# Reguladores.net
KiCad netlist of a schematic drawn in Altium Designer
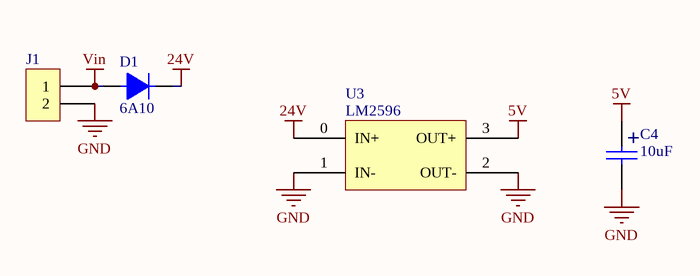
[diagram p0: Reguladores.SchDoc]

(export (version "E")
  (design (tool "Eeschema 10.0.6"))
  (components
    (comp (ref "C4") (value "10uF") (footprint "CAP.ELEC") (libsource (lib "LIBPIOIX") (part "CAPPOL")))
    (comp (ref "D1") (value "6A10") (footprint "DO214AC") (libsource (lib "LIBPIOIX") (part "DIODO")))
    (comp (ref "J1")
      (value "BORNERA 2")
      (footprint "BORNERA2")
      (libsource (lib "LIBPIOIX") (part "BORNERA 2"))
    )
    (comp (ref "U3")
      (value "LM2596")
      (footprint "LM2596 DC TO DC CONVERTER MODULE")
      (libsource (lib "Esquematicos") (part "LM2596"))
    )
  )
  (nets
    (net (code "1") (name "5V") (class "Default")
      (node (ref "C4") (pin "1") (pinfunction "1_1") (pintype "passive"))
      (node (ref "U3") (pin "3") (pinfunction "OUT+_3") (pintype "passive"))
    )
    (net (code "2") (name "24V") (class "Default")
      (node (ref "D1") (pin "2") (pinfunction "2_2") (pintype "passive"))
      (node (ref "U3") (pin "0") (pinfunction "IN+_0") (pintype "passive"))
    )
    (net (code "3") (name "GND") (class "Default")
      (node (ref "C4") (pin "2") (pinfunction "2_2") (pintype "passive"))
      (node (ref "J1") (pin "2") (pinfunction "2_2") (pintype "passive"))
      (node (ref "U3") (pin "1") (pinfunction "IN-_1") (pintype "passive"))
      (node (ref "U3") (pin "2") (pinfunction "OUT-_2") (pintype "passive"))
    )
    (net (code "4") (name "Vin") (class "Default")
      (node (ref "D1") (pin "1") (pinfunction "1_1") (pintype "passive"))
      (node (ref "J1") (pin "1") (pinfunction "1_1") (pintype "passive"))
    )
  )
)
